# STO.net
KiCad netlist of a schematic drawn in Altium Designer
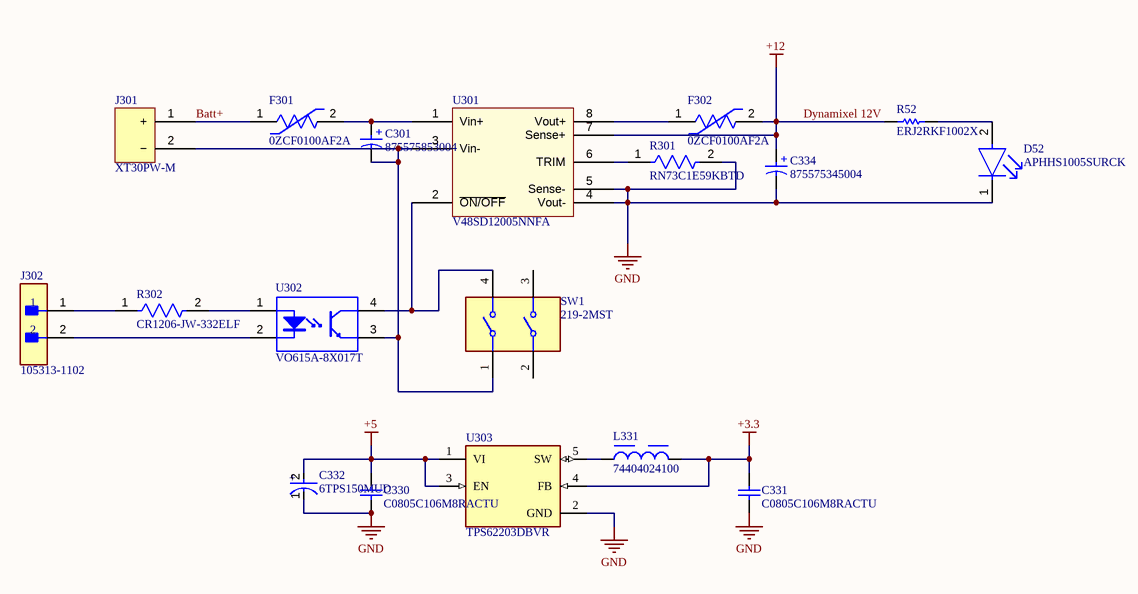
[diagram p0: STO.SchDoc]

(export (version "E")
  (design (tool "Eeschema 10.0.6"))
  (components
    (comp (ref "C301")
      (value "875575853004")
      (footprint "WCAP-HSG5_D8H10.5")
      (description "875575853004 Cap, 47Uf, 63V, Alu Elec, Hybrid, Smd Rohs Compliant: Yes")
      (libsource (lib "Altium Content Vault") (part "Capacitor_Polarized"))
    )
    (comp (ref "C330")
      (value "C0805C106M8RACTU")
      (footprint "CAPC2013X140X50NL20T25")
      (fields (field (name "MANUFACTURER") "Kemet"))
      (libsource (lib "Altium Content Vault") (part "CAP"))
    )
    (comp (ref "C331")
      (value "C0805C106M8RACTU")
      (footprint "CAPC2013X140X50NL20T25")
      (fields (field (name "MANUFACTURER") "Kemet"))
      (libsource (lib "Altium Content Vault") (part "CAP"))
    )
    (comp (ref "C332")
      (value "6TPS150MUD")
      (footprint "FP-POSCAP-B1S-MFG")
      (description "Molded Tantalum Polymer Capacitor 150uF 20% 6.3V life 2000Hours SMD 1411")
      (libsource (lib "Altium Content Vault") (part "203bc49f2ac43e59fd269a8c329ed05"))
    )
    (comp (ref "C334")
      (value "875575345004")
      (footprint "WCAP-HSG5_D6.3H7.7")
      (description "875575345004 Cap, 220Uf, 16V, Alu Elec, Hybrid, Smd Rohs Compliant: Yes")
      (libsource (lib "Altium Content Vault") (part "Capacitor_Polarized"))
    )
    (comp (ref "D52")
      (value "APHHS1005SURCK")
      (footprint "FP-APHHS1005SURCK-MFG")
      (description "LED RED CLEAR CHIP SMD")
      (libsource (lib "Altium Content Vault") (part "8706943c75ba83719d021d2fdc84c58"))
    )
    (comp (ref "F301")
      (value "0ZCF0100AF2A")
      (footprint "FP-0ZCF0100AF2A-MFG")
      (description "PTC RESET FUSE 60V 1A 2920")
      (libsource (lib "Altium Content Vault") (part "1c6d77a0208143737455a0c7eb396be"))
    )
    (comp (ref "F302")
      (value "0ZCF0100AF2A")
      (footprint "FP-0ZCF0100AF2A-MFG")
      (description "PTC RESET FUSE 60V 1A 2920")
      (libsource (lib "Altium Content Vault") (part "1c6d77a0208143737455a0c7eb396be"))
    )
    (comp (ref "J301")
      (value "XT30PW-M")
      (footprint "XT30PW_M")
      (description "Amass XT30 RA TH male header")
      (fields (field (name "MANUFACTURER") "Amass"))
      (libsource (lib "DMR_common_lib") (part "XT30PW-M"))
    )
    (comp (ref "J302")
      (value "105313-1102")
      (footprint "FP-105313-1102-MFG")
      (description "CONN HEADER R/A 2POS 2.5MM")
      (libsource (lib "Altium Content Vault") (part "3bc925449376181038e59eaffc5286c"))
    )
    (comp (ref "L331")
      (value "74404024100")
      (footprint "WE-LQS_2512")
      (fields (field (name "TOLERANCE") "20%"))
      (libsource (lib "Altium Content Vault") (part "Inductor - 3"))
    )
    (comp (ref "R52")
      (value "ERJ2RKF1002X")
      (footprint "RESC1005X40X25LL05T05")
      (description "Chip Resistor, 10 KOhm, +/- 1%, 0.1 W, -55 to 155 degC, 0402 (1005 Metric), RoHS, Tape and Reel")
      (fields (field (name "TOLERANCE") "1%") (field (name "MANUFACTURER") "Panasonic"))
      (libsource (lib "Altium Content Vault") (part "RES-2"))
    )
    (comp (ref "R301")
      (value "RN73C1E59KBTD")
      (footprint "FP-RN731E-MFG")
      (description "Res Thin Film 0402 59KΩ 0.1% 1/16W 10ppm/°C Molded SMD")
      (fields
        (field (name "MANUFACTURER") "TE Connectivity")
        (field (name "OCTOPART") "https://octopart.com/rn73c1e59kbtd-te+connectivity-76703336")
      )
      (libsource (lib "Altium Content Vault") (part "1029c3af85768c4190bb7ad29bc67b5"))
    )
    (comp (ref "R302")
      (value "CR1206-JW-332ELF")
      (footprint "FP-CR1206-IPC_B")
      (description "Thick Film Chip Resistors 1206 3.3kΩ 0.25W 5% 200ppm/°C")
      (fields (field (name "TOLERANCE") "5%"))
      (libsource (lib "Altium Content Vault") (part "1029c3af85768c4190bb7ad29bc67b5"))
    )
    (comp (ref "SW1")
      (value "219-2MST")
      (footprint "FP-219-2MST-MFG")
      (description "SWITCH SLIDE DIP SPST 100MA 20V")
      (libsource (lib "Altium Content Vault") (part "0c6b50a108966649035016ba9caaaf4"))
    )
    (comp (ref "U301")
      (value "V48SD12005NNFA")
      (footprint "1/16 Brick")
      (libsource (lib "Schlib1") (part "V48SD12005NNFA"))
    )
    (comp (ref "U302")
      (value "VO615A-8X017T")
      (footprint "VISH-VO615A-XX017T_V")
      (fields (field (name "MANUFACTURER") "Vishay"))
      (libsource (lib "Altium Content Vault") (part "OPTO-AKEC-4"))
    )
    (comp (ref "U303")
      (value "TPS62203DBVR")
      (footprint "FP-DBV0005A-IPC_B")
      (description "IC REG BUCK 3.3V 300MA SOT23-5")
      (libsource (lib "Altium Content Vault") (part "5705ee1261737306bdf98f885a4cd50"))
    )
  )
  (nets
    (net (code "1") (name "+3.3") (class "Default")
      (node (ref "C331") (pin "2") (pinfunction "2_2") (pintype "passive"))
      (node (ref "L331") (pin "2") (pinfunction "2_2") (pintype "passive"))
      (node (ref "U303") (pin "4") (pinfunction "FB_4") (pintype "input"))
    )
    (net (code "2") (name "+5") (class "Default")
      (node (ref "C330") (pin "1") (pinfunction "1_1") (pintype "passive"))
      (node (ref "C332") (pin "2") (pinfunction "A_2") (pintype "passive"))
      (node (ref "U303") (pin "1") (pinfunction "VI_1") (pintype "power_in"))
      (node (ref "U303") (pin "3") (pinfunction "EN_3") (pintype "input"))
    )
    (net (code "3") (name "+12") (class "Default")
      (node (ref "C334") (pin "1") (pinfunction "P_1") (pintype "passive"))
      (node (ref "F302") (pin "2") (pinfunction "2_2") (pintype "passive"))
      (node (ref "R52") (pin "2") (pinfunction "2_2") (pintype "passive"))
      (node (ref "U301") (pin "7") (pinfunction "Sense+_7") (pintype "passive"))
    )
    (net (code "4") (name "/Batt+") (class "Default")
      (node (ref "F301") (pin "1") (pinfunction "1_1") (pintype "passive"))
      (node (ref "J301") (pin "1") (pinfunction "+_1") (pintype "passive"))
    )
    (net (code "5") (name "GND") (class "Default")
      (node (ref "C330") (pin "2") (pinfunction "2_2") (pintype "passive"))
      (node (ref "C331") (pin "1") (pinfunction "1_1") (pintype "passive"))
      (node (ref "C332") (pin "1") (pinfunction "C_1") (pintype "passive"))
      (node (ref "C334") (pin "2") (pinfunction "N_2") (pintype "passive"))
      (node (ref "D52") (pin "1") (pinfunction "C_1") (pintype "passive"))
      (node (ref "R301") (pin "2") (pinfunction "2_2") (pintype "passive"))
      (node (ref "U301") (pin "4") (pinfunction "Vout-_4") (pintype "passive"))
      (node (ref "U301") (pin "5") (pinfunction "Sense-_5") (pintype "passive"))
      (node (ref "U303") (pin "2") (pinfunction "GND_2") (pintype "power_in"))
    )
    (net (code "6") (name "Net-(C301-N)") (class "Default")
      (node (ref "C301") (pin "2") (pinfunction "N_2") (pintype "passive"))
      (node (ref "J301") (pin "2") (pinfunction "−_2") (pintype "passive"))
      (node (ref "SW1") (pin "1") (pinfunction "1_1") (pintype "passive"))
      (node (ref "U301") (pin "3") (pinfunction "Vin-_3") (pintype "passive"))
      (node (ref "U302") (pin "3") (pinfunction "EMITTER_3") (pintype "passive"))
    )
    (net (code "7") (name "Net-(C301-P)") (class "Default")
      (node (ref "C301") (pin "1") (pinfunction "P_1") (pintype "passive"))
      (node (ref "F301") (pin "2") (pinfunction "2_2") (pintype "passive"))
      (node (ref "U301") (pin "1") (pinfunction "Vin+_1") (pintype "passive"))
    )
    (net (code "8") (name "Net-(D52-A)") (class "Default")
      (node (ref "D52") (pin "2") (pinfunction "A_2") (pintype "passive"))
      (node (ref "R52") (pin "1") (pinfunction "1_1") (pintype "passive"))
    )
    (net (code "9") (name "Net-(J302-Pad1)") (class "Default")
      (node (ref "J302") (pin "1") (pinfunction "1_1") (pintype "passive"))
      (node (ref "R302") (pin "1") (pinfunction "1_1") (pintype "passive"))
    )
    (net (code "10") (name "Net-(U301-ON{slash}OFF)") (class "Default")
      (node (ref "SW1") (pin "4") (pinfunction "4_4") (pintype "passive"))
      (node (ref "U301") (pin "2") (pinfunction "ON/OFF_2") (pintype "passive"))
      (node (ref "U302") (pin "4") (pinfunction "COLLECTOR_4") (pintype "passive"))
    )
    (net (code "11") (name "Net-(U301-TRIM)") (class "Default")
      (node (ref "R301") (pin "1") (pinfunction "1_1") (pintype "passive"))
      (node (ref "U301") (pin "6") (pinfunction "TRIM_6") (pintype "passive"))
    )
    (net (code "12") (name "Net-(U301-Vout+)") (class "Default")
      (node (ref "F302") (pin "1") (pinfunction "1_1") (pintype "passive"))
      (node (ref "U301") (pin "8") (pinfunction "Vout+_8") (pintype "passive"))
    )
    (net (code "13") (name "Net-(U302-ANODE)") (class "Default")
      (node (ref "R302") (pin "2") (pinfunction "2_2") (pintype "passive"))
      (node (ref "U302") (pin "1") (pinfunction "ANODE_1") (pintype "passive"))
    )
    (net (code "14") (name "Net-(U302-CATHODE)") (class "Default")
      (node (ref "J302") (pin "2") (pinfunction "2_2") (pintype "passive"))
      (node (ref "U302") (pin "2") (pinfunction "CATHODE_2") (pintype "passive"))
    )
    (net (code "15") (name "Net-(U303-SW)") (class "Default")
      (node (ref "L331") (pin "1") (pinfunction "1_1") (pintype "passive"))
      (node (ref "U303") (pin "5") (pinfunction "SW_5") (pintype "bidirectional"))
    )
    (net (code "16") (name "unconnected-(SW1-Pad2)") (class "Default")
      (node (ref "SW1") (pin "2") (pinfunction "2_2") (pintype "passive"))
    )
    (net (code "17") (name "unconnected-(SW1-Pad3)") (class "Default")
      (node (ref "SW1") (pin "3") (pinfunction "3_3") (pintype "passive"))
    )
  )
)
